# BANK2.net
KiCad netlist of a schematic drawn in Altium Designer
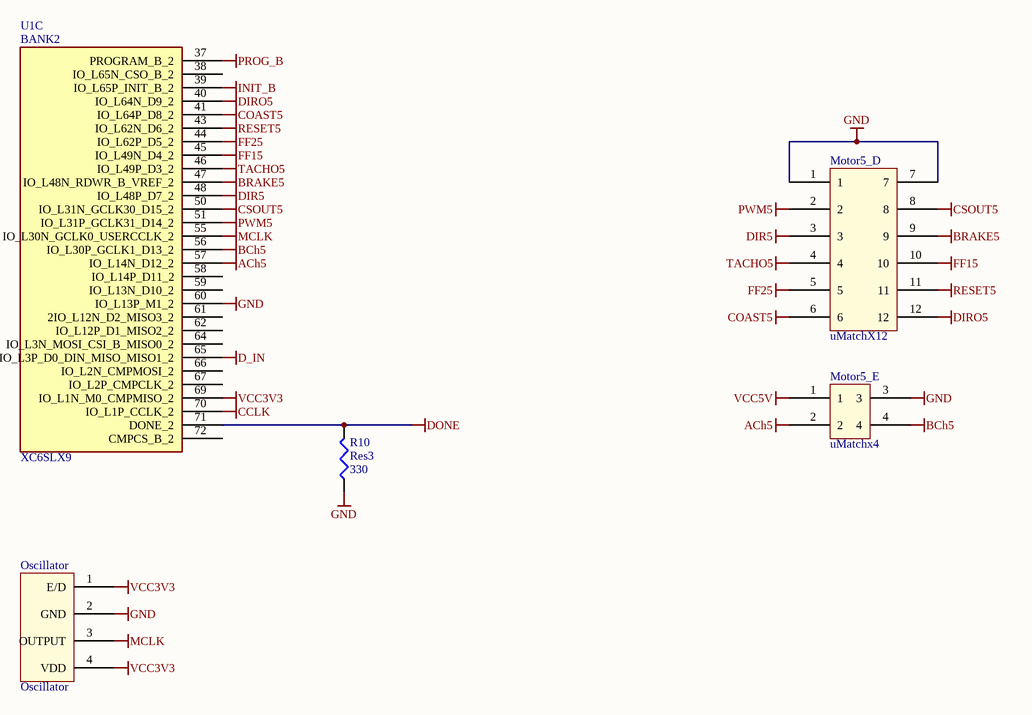
[diagram p0: BANK2.SchDoc]

(export (version "E")
  (design (tool "Eeschema 10.0.6"))
  (components
    (comp (ref "Motor5_D")
      (value "uMatchX12")
      (footprint "uMatchX12")
      (libsource (lib "Mainboard_component_schematics") (part "uMatchX12"))
    )
    (comp (ref "Motor5_E")
      (value "uMatchx4")
      (footprint "Micromatch x4")
      (libsource (lib "Mainboard_component_schematics") (part "uMatchx4"))
    )
    (comp (ref "Oscillator")
      (value "Oscillator")
      (footprint "osc_FOOTPRINT")
      (description "Fox_osc_100MHz")
      (libsource (lib "Mainboard_component_schematics") (part "Oscillator"))
    )
    (comp (ref "R10")
      (value "Res3")
      (footprint "J1-0603")
      (description "Resistor")
      (fields (field (name "ALTIUM_VALUE") "330") (field (name "PUBLISHER") "Altium Limited"))
      (libsource (lib "Miscellaneous Devices") (part "Res3"))
    )
    (comp (ref "U1")
      (value "XC6SLX9")
      (footprint "XC6SLX9")
      (description "Imported")
      (libsource (lib "Mainboard_component_schematics") (part "C6SLX9"))
    )
  )
  (nets
    (net (code "1") (name "ACh5") (class "Default")
      (node (ref "Motor5_E") (pin "2") (pinfunction "2_2") (pintype "passive"))
      (node (ref "U1") (pin "57") (pinfunction "IO_L14N_D12_2_57") (pintype "passive"))
    )
    (net (code "2") (name "BCh5") (class "Default")
      (node (ref "Motor5_E") (pin "4") (pinfunction "4_4") (pintype "passive"))
      (node (ref "U1") (pin "56") (pinfunction "IO_L30P_GCLK1_D13_2_56") (pintype "passive"))
    )
    (net (code "3") (name "BRAKE5") (class "Default")
      (node (ref "Motor5_D") (pin "9") (pinfunction "9_9") (pintype "passive"))
      (node (ref "U1") (pin "47") (pinfunction "IO_L48N_RDWR_B_VREF_2_47") (pintype "passive"))
    )
    (net (code "4") (name "CCLK") (class "Default")
      (node (ref "U1") (pin "70") (pinfunction "IO_L1P_CCLK_2_70") (pintype "passive"))
    )
    (net (code "5") (name "COAST5") (class "Default")
      (node (ref "Motor5_D") (pin "6") (pinfunction "6_6") (pintype "passive"))
      (node (ref "U1") (pin "41") (pinfunction "IO_L64P_D8_2_41") (pintype "passive"))
    )
    (net (code "6") (name "CSOUT5") (class "Default")
      (node (ref "Motor5_D") (pin "8") (pinfunction "8_8") (pintype "passive"))
      (node (ref "U1") (pin "50") (pinfunction "IO_L31N_GCLK30_D15_2_50") (pintype "passive"))
    )
    (net (code "7") (name "DIR5") (class "Default")
      (node (ref "Motor5_D") (pin "3") (pinfunction "3_3") (pintype "passive"))
      (node (ref "U1") (pin "48") (pinfunction "IO_L48P_D7_2_48") (pintype "passive"))
    )
    (net (code "8") (name "DIRO5") (class "Default")
      (node (ref "Motor5_D") (pin "12") (pinfunction "12_12") (pintype "passive"))
      (node (ref "U1") (pin "40") (pinfunction "IO_L64N_D9_2_40") (pintype "passive"))
    )
    (net (code "9") (name "DONE") (class "Default")
      (node (ref "R10") (pin "2") (pinfunction "2_2") (pintype "passive"))
      (node (ref "U1") (pin "71") (pinfunction "DONE_2_71") (pintype "passive"))
    )
    (net (code "10") (name "D_IN") (class "Default")
      (node (ref "U1") (pin "65") (pinfunction "IO_L3P_D0_DIN_MISO_MISO1_2_65") (pintype "passive"))
    )
    (net (code "11") (name "FF15") (class "Default")
      (node (ref "Motor5_D") (pin "10") (pinfunction "10_10") (pintype "passive"))
      (node (ref "U1") (pin "45") (pinfunction "IO_L49N_D4_2_45") (pintype "passive"))
    )
    (net (code "12") (name "FF25") (class "Default")
      (node (ref "Motor5_D") (pin "5") (pinfunction "5_5") (pintype "passive"))
      (node (ref "U1") (pin "44") (pinfunction "IO_L62P_D5_2_44") (pintype "passive"))
    )
    (net (code "13") (name "GND") (class "Default")
      (node (ref "Motor5_D") (pin "1") (pinfunction "1_1") (pintype "passive"))
      (node (ref "Motor5_D") (pin "7") (pinfunction "7_7") (pintype "passive"))
      (node (ref "Motor5_E") (pin "3") (pinfunction "3_3") (pintype "passive"))
      (node (ref "Oscillator") (pin "2") (pinfunction "GND_2") (pintype "passive"))
      (node (ref "R10") (pin "1") (pinfunction "1_1") (pintype "passive"))
      (node (ref "U1") (pin "60") (pinfunction "IO_L13P_M1_2_60") (pintype "passive"))
    )
    (net (code "14") (name "INIT_B") (class "Default")
      (node (ref "U1") (pin "39") (pinfunction "IO_L65P_INIT_B_2_39") (pintype "passive"))
    )
    (net (code "15") (name "MCLK") (class "Default")
      (node (ref "Oscillator") (pin "3") (pinfunction "OUTPUT_3") (pintype "passive"))
      (node (ref "U1") (pin "55") (pinfunction "IO_L30N_GCLK0_USERCCLK_2_55") (pintype "passive"))
    )
    (net (code "16") (name "PROG_B") (class "Default")
      (node (ref "U1") (pin "37") (pinfunction "PROGRAM_B_2_37") (pintype "passive"))
    )
    (net (code "17") (name "PWM5") (class "Default")
      (node (ref "Motor5_D") (pin "2") (pinfunction "2_2") (pintype "passive"))
      (node (ref "U1") (pin "51") (pinfunction "IO_L31P_GCLK31_D14_2_51") (pintype "passive"))
    )
    (net (code "18") (name "RESET5") (class "Default")
      (node (ref "Motor5_D") (pin "11") (pinfunction "11_11") (pintype "passive"))
      (node (ref "U1") (pin "43") (pinfunction "IO_L62N_D6_2_43") (pintype "passive"))
    )
    (net (code "19") (name "TACHO5") (class "Default")
      (node (ref "Motor5_D") (pin "4") (pinfunction "4_4") (pintype "passive"))
      (node (ref "U1") (pin "46") (pinfunction "IO_L49P_D3_2_46") (pintype "passive"))
    )
    (net (code "20") (name "VCC3V3") (class "Default")
      (node (ref "Oscillator") (pin "1") (pinfunction "E/D_1") (pintype "passive"))
      (node (ref "Oscillator") (pin "4") (pinfunction "VDD_4") (pintype "passive"))
      (node (ref "U1") (pin "69") (pinfunction "IO_L1N_M0_CMPMISO_2_69") (pintype "passive"))
    )
    (net (code "21") (name "VCC5V") (class "Default")
      (node (ref "Motor5_E") (pin "1") (pinfunction "1_1") (pintype "passive"))
    )
    (net (code "22") (name "unconnected-(U1C-2IO_L12N_D2_MISO3_2-Pad61)") (class "Default")
      (node (ref "U1") (pin "61") (pinfunction "2IO_L12N_D2_MISO3_2_61") (pintype "passive"))
    )
    (net (code "23") (name "unconnected-(U1C-CMPCS_B_2-Pad72)") (class "Default")
      (node (ref "U1") (pin "72") (pinfunction "CMPCS_B_2_72") (pintype "passive"))
    )
    (net (code "24") (name "unconnected-(U1C-IO_L2N_CMPMOSI_2-Pad66)") (class "Default")
      (node (ref "U1") (pin "66") (pinfunction "IO_L2N_CMPMOSI_2_66") (pintype "passive"))
    )
    (net (code "25") (name "unconnected-(U1C-IO_L2P_CMPCLK_2-Pad67)") (class "Default")
      (node (ref "U1") (pin "67") (pinfunction "IO_L2P_CMPCLK_2_67") (pintype "passive"))
    )
    (net (code "26") (name "unconnected-(U1C-IO_L3N_MOSI_CSI_B_MISO0_2-Pad64)") (class "Default")
      (node (ref "U1") (pin "64") (pinfunction "IO_L3N_MOSI_CSI_B_MISO0_2_64") (pintype "passive"))
    )
    (net (code "27") (name "unconnected-(U1C-IO_L12P_D1_MISO2_2-Pad62)") (class "Default")
      (node (ref "U1") (pin "62") (pinfunction "IO_L12P_D1_MISO2_2_62") (pintype "passive"))
    )
    (net (code "28") (name "unconnected-(U1C-IO_L13N_D10_2-Pad59)") (class "Default")
      (node (ref "U1") (pin "59") (pinfunction "IO_L13N_D10_2_59") (pintype "passive"))
    )
    (net (code "29") (name "unconnected-(U1C-IO_L14P_D11_2-Pad58)") (class "Default")
      (node (ref "U1") (pin "58") (pinfunction "IO_L14P_D11_2_58") (pintype "passive"))
    )
    (net (code "30") (name "unconnected-(U1C-IO_L65N_CSO_B_2-Pad38)") (class "Default")
      (node (ref "U1") (pin "38") (pinfunction "IO_L65N_CSO_B_2_38") (pintype "passive"))
    )
  )
)
